# EEpromConfig.net
KiCad netlist of a schematic drawn in Altium Designer
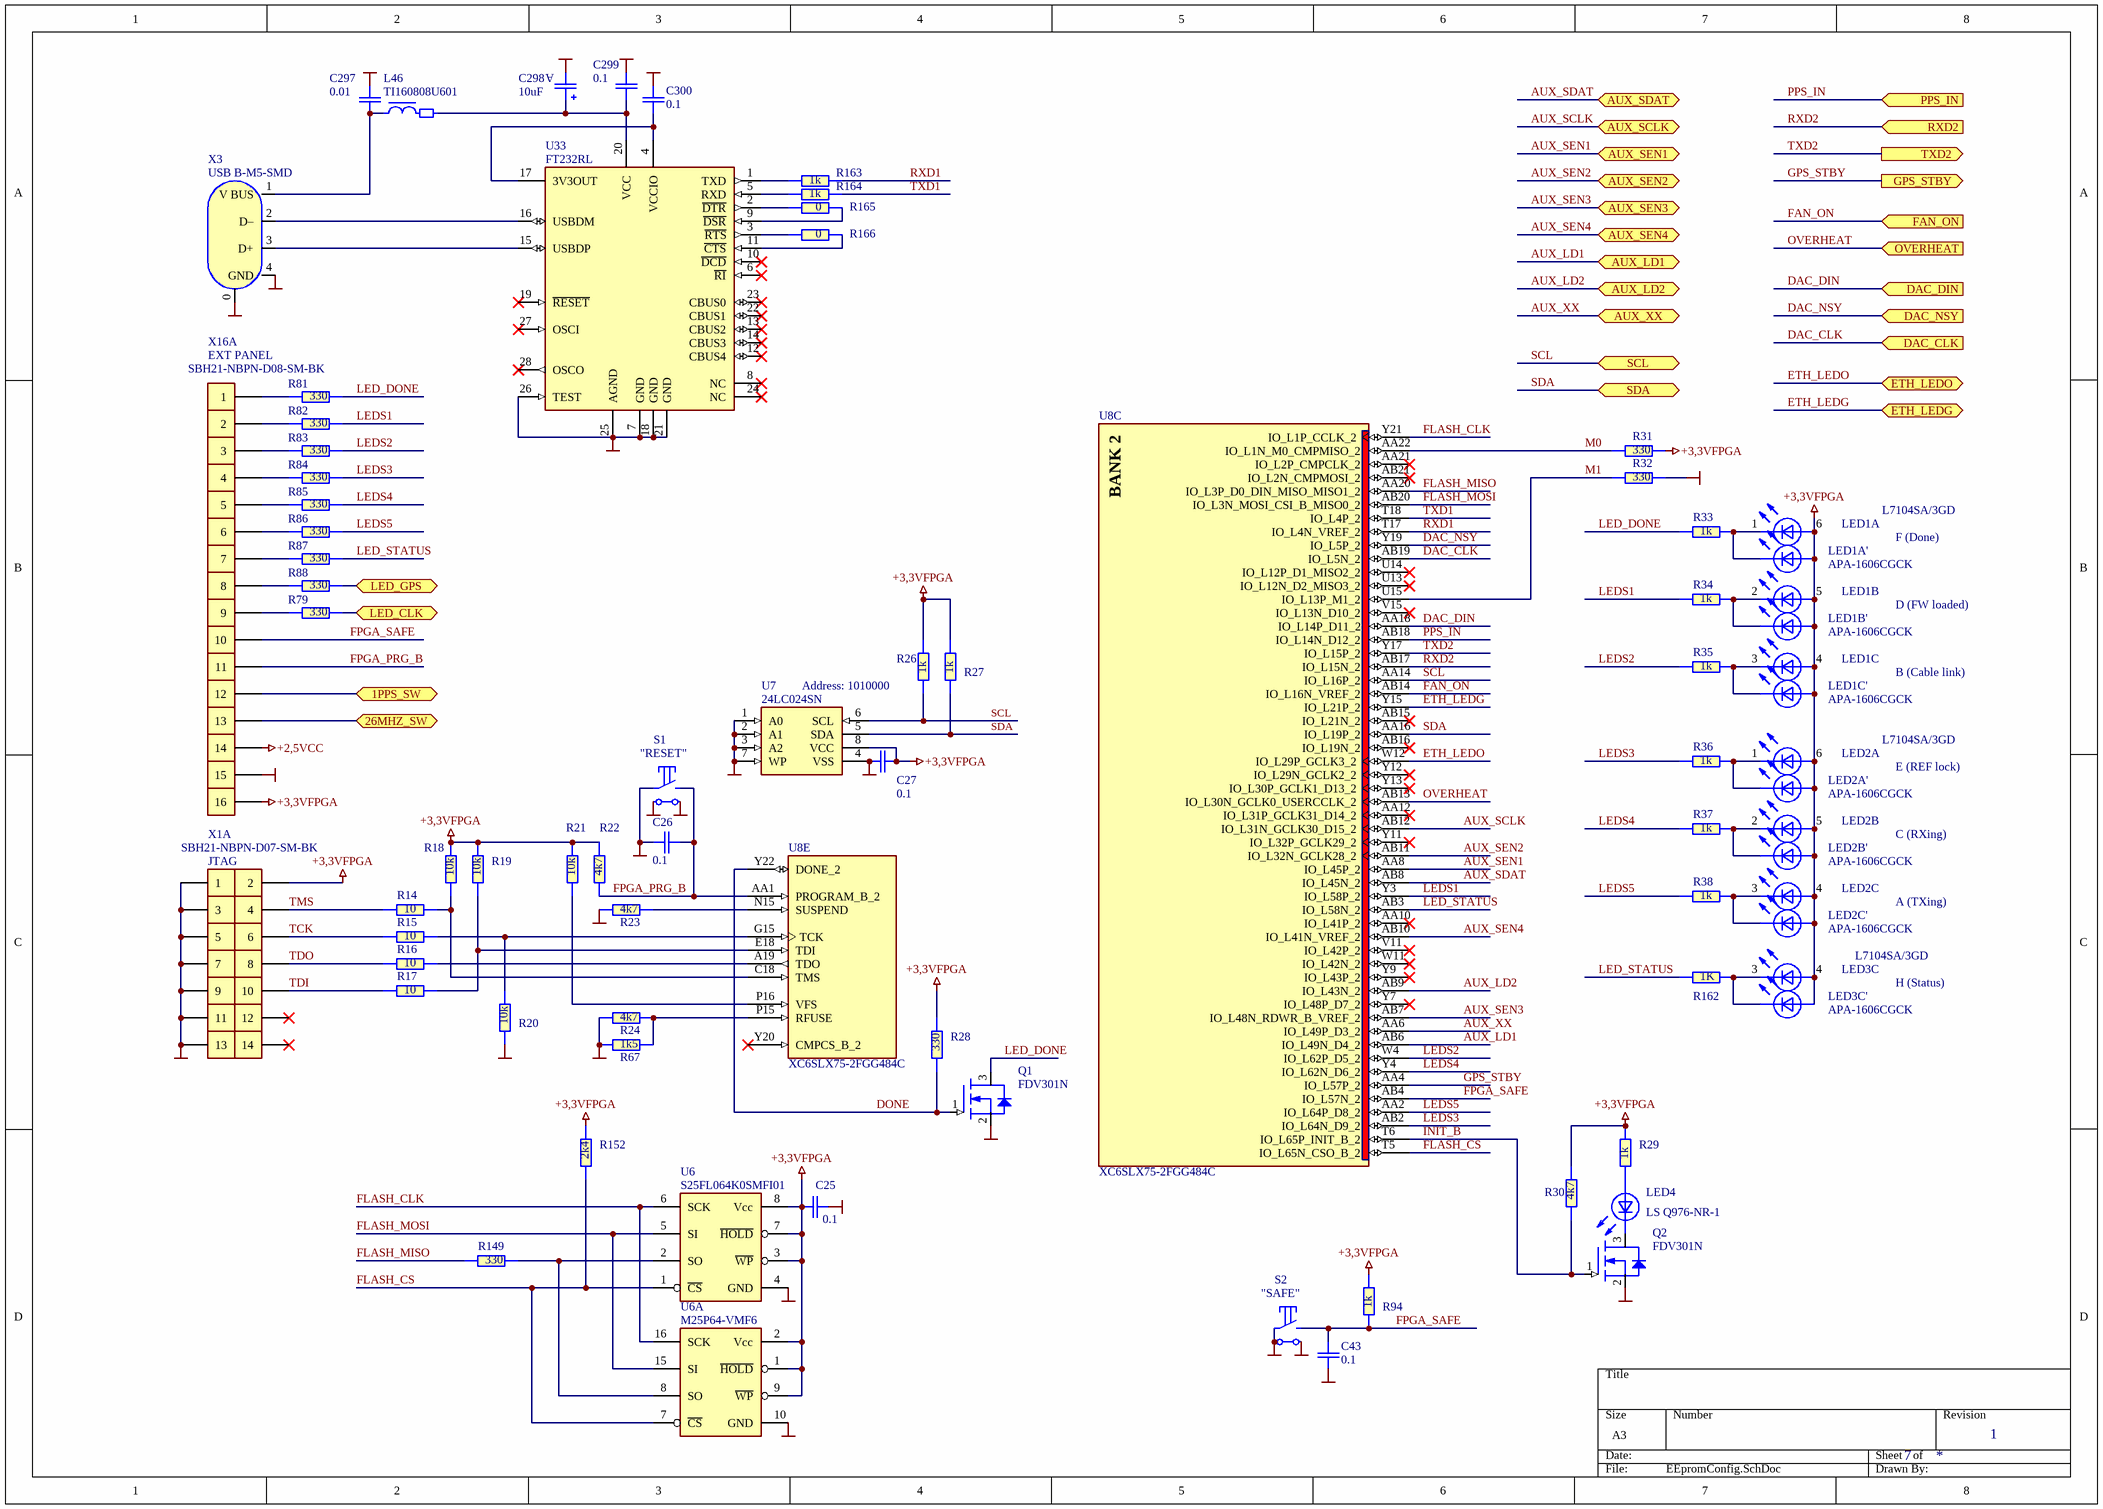
[diagram p0: EEpromConfig.SchDoc]

(export (version "E")
  (design (tool "Eeschema 10.0.6"))
  (components
    (comp (ref "C25")
      (value "0.1")
      (footprint "C0402-Phillips")
      (description "Конденсатор")
      (fields (field (name "MANUFACTURER") "MURATA") (field (name "TOLERANCE") "20%"))
      (libsource (lib "Capacitors") (part "C0402"))
    )
    (comp (ref "C26")
      (value "0.1")
      (footprint "C0402-Phillips")
      (description "Конденсатор")
      (fields (field (name "MANUFACTURER") "MURATA") (field (name "TOLERANCE") "20%"))
      (libsource (lib "Capacitors") (part "C0402"))
    )
    (comp (ref "C27")
      (value "0.1")
      (footprint "C0402-Phillips")
      (description "Конденсатор")
      (fields (field (name "MANUFACTURER") "MURATA") (field (name "TOLERANCE") "20%"))
      (libsource (lib "Capacitors") (part "C0402"))
    )
    (comp (ref "C43")
      (value "0.1")
      (footprint "C0402-Phillips")
      (description "Конденсатор")
      (fields (field (name "MANUFACTURER") "MURATA") (field (name "TOLERANCE") "20%"))
      (libsource (lib "Capacitors") (part "C0402"))
    )
    (comp (ref "C297")
      (value "0.01")
      (footprint "C0402-Phillips")
      (description "Конденсатор")
      (fields (field (name "MANUFACTURER") "MURATA") (field (name "TOLERANCE") "20%"))
      (libsource (lib "Capacitors") (part "C0402"))
    )
    (comp (ref "C298")
      (value "10uF")
      (footprint "CA3216")
      (description "Конденсатор")
      (fields (field (name "MANUFACTURER") "SPRAGUE"))
      (libsource (lib "Capacitors") (part "CA3216"))
    )
    (comp (ref "C299")
      (value "0.1")
      (footprint "C0402-Phillips")
      (description "Конденсатор")
      (fields (field (name "MANUFACTURER") "MURATA") (field (name "TOLERANCE") "20%"))
      (libsource (lib "Capacitors") (part "C0402"))
    )
    (comp (ref "C300")
      (value "0.1")
      (footprint "C0402-Phillips")
      (description "Конденсатор")
      (fields (field (name "MANUFACTURER") "MURATA") (field (name "TOLERANCE") "20%"))
      (libsource (lib "Capacitors") (part "C0402"))
    )
    (comp (ref "L46")
      (value "TI160808U601")
      (footprint "Ti160808-Phillips")
      (description "Дроссель ЭМС")
      (fields (field (name "MANUFACTURER") "MURATA"))
      (libsource (lib "altium-import") (part "root_0_TI160808_"))
    )
    (comp (ref "LED1")
      (value "L7104SA/3GD")
      (footprint "L-7104SA/3")
      (description "Светодиод")
      (fields (field (name "MANUFACTURER") "KINGBRIGTH"))
      (libsource (lib "Diods") (part "L7104SA/3"))
    )
    (comp (ref "LED1A'")
      (value "APA-1606CGCK")
      (footprint "KPA-1606g")
      (description "Светодиод")
      (fields (field (name "MANUFACTURER") "Kingbright"))
      (libsource (lib "Diods") (part "KPA-1606"))
    )
    (comp (ref "LED1B'")
      (value "APA-1606CGCK")
      (footprint "KPA-1606g")
      (description "Светодиод")
      (fields (field (name "MANUFACTURER") "Kingbright"))
      (libsource (lib "Diods") (part "KPA-1606"))
    )
    (comp (ref "LED1C'")
      (value "APA-1606CGCK")
      (footprint "KPA-1606g")
      (description "Светодиод")
      (fields (field (name "MANUFACTURER") "Kingbright"))
      (libsource (lib "Diods") (part "KPA-1606"))
    )
    (comp (ref "LED2")
      (value "L7104SA/3GD")
      (footprint "L-7104SA/3")
      (description "Светодиод")
      (fields (field (name "MANUFACTURER") "KINGBRIGTH"))
      (libsource (lib "Diods") (part "L7104SA/3"))
    )
    (comp (ref "LED2A'")
      (value "APA-1606CGCK")
      (footprint "KPA-1606g")
      (description "Светодиод")
      (fields (field (name "MANUFACTURER") "Kingbright"))
      (libsource (lib "Diods") (part "KPA-1606"))
    )
    (comp (ref "LED2B'")
      (value "APA-1606CGCK")
      (footprint "KPA-1606g")
      (description "Светодиод")
      (fields (field (name "MANUFACTURER") "Kingbright"))
      (libsource (lib "Diods") (part "KPA-1606"))
    )
    (comp (ref "LED2C'")
      (value "APA-1606CGCK")
      (footprint "KPA-1606g")
      (description "Светодиод")
      (fields (field (name "MANUFACTURER") "Kingbright"))
      (libsource (lib "Diods") (part "KPA-1606"))
    )
    (comp (ref "LED3")
      (value "L7104SA/3GD")
      (footprint "L-7104SA/3")
      (description "Светодиод")
      (fields (field (name "MANUFACTURER") "KINGBRIGTH"))
      (libsource (lib "Diods") (part "L7104SA/3"))
    )
    (comp (ref "LED3C'")
      (value "APA-1606CGCK")
      (footprint "KPA-1606g")
      (description "Светодиод")
      (fields (field (name "MANUFACTURER") "Kingbright"))
      (libsource (lib "Diods") (part "KPA-1606"))
    )
    (comp (ref "LED4")
      (value "LS Q976-NR-1")
      (footprint "LED-0603y")
      (description "LED SMD")
      (fields (field (name "MANUFACTURER") "OSRAM Opto Semiconductors Inc"))
      (libsource (lib "altium-import") (part "root_2_LED0603_"))
    )
    (comp (ref "Q1")
      (value "FDV301N")
      (footprint "SOT23-Philips")
      (description "Транзистор")
      (fields (field (name "MANUFACTURER") "Fairchild"))
      (libsource (lib "Transistors") (part "FDV301N"))
    )
    (comp (ref "Q2")
      (value "FDV301N")
      (footprint "SOT23-Philips")
      (description "Транзистор")
      (fields (field (name "MANUFACTURER") "Fairchild"))
      (libsource (lib "Transistors") (part "FDV301N"))
    )
    (comp (ref "R14")
      (value "10")
      (footprint "R0603-PHILLIPS")
      (description "Резистор")
      (fields (field (name "MANUFACTURER") "YAGEO") (field (name "TOLERANCE") "5%"))
      (libsource (lib "altium-import") (part "root_1_R0603_"))
    )
    (comp (ref "R15")
      (value "10")
      (footprint "R0603-PHILLIPS")
      (description "Резистор")
      (fields (field (name "MANUFACTURER") "YAGEO") (field (name "TOLERANCE") "5%"))
      (libsource (lib "altium-import") (part "root_1_R0603_"))
    )
    (comp (ref "R16")
      (value "10")
      (footprint "R0603-PHILLIPS")
      (description "Резистор")
      (fields (field (name "MANUFACTURER") "YAGEO") (field (name "TOLERANCE") "5%"))
      (libsource (lib "altium-import") (part "root_1_R0603_"))
    )
    (comp (ref "R17")
      (value "10")
      (footprint "R0603-PHILLIPS")
      (description "Резистор")
      (fields (field (name "MANUFACTURER") "YAGEO") (field (name "TOLERANCE") "5%"))
      (libsource (lib "altium-import") (part "root_1_R0603_"))
    )
    (comp (ref "R18")
      (value "10k")
      (footprint "R0603-PHILLIPS")
      (description "Резистор")
      (fields (field (name "MANUFACTURER") "YAGEO") (field (name "TOLERANCE") "5%"))
      (libsource (lib "altium-import") (part "root_0_R0603_"))
    )
    (comp (ref "R19")
      (value "10k")
      (footprint "R0603-PHILLIPS")
      (description "Резистор")
      (fields (field (name "MANUFACTURER") "YAGEO") (field (name "TOLERANCE") "5%"))
      (libsource (lib "altium-import") (part "root_0_R0603_"))
    )
    (comp (ref "R20")
      (value "10k")
      (footprint "R0603-PHILLIPS")
      (description "Резистор")
      (fields (field (name "MANUFACTURER") "YAGEO") (field (name "TOLERANCE") "5%"))
      (libsource (lib "altium-import") (part "root_0_R0603_"))
    )
    (comp (ref "R21")
      (value "10k")
      (footprint "R0603-PHILLIPS")
      (description "Резистор")
      (fields (field (name "MANUFACTURER") "YAGEO") (field (name "TOLERANCE") "5%"))
      (libsource (lib "altium-import") (part "root_0_R0603_"))
    )
    (comp (ref "R22")
      (value "4k7")
      (footprint "R0603-PHILLIPS")
      (description "Резистор")
      (fields (field (name "MANUFACTURER") "YAGEO") (field (name "TOLERANCE") "5%"))
      (libsource (lib "altium-import") (part "root_0_R0603_"))
    )
    (comp (ref "R23")
      (value "4k7")
      (footprint "R0603-PHILLIPS")
      (description "Резистор")
      (fields (field (name "MANUFACTURER") "YAGEO") (field (name "TOLERANCE") "5%"))
      (libsource (lib "altium-import") (part "root_1_R0603_"))
    )
    (comp (ref "R24")
      (value "4k7")
      (footprint "R0603-PHILLIPS")
      (description "Резистор")
      (fields (field (name "MANUFACTURER") "YAGEO") (field (name "TOLERANCE") "5%"))
      (libsource (lib "altium-import") (part "root_1_R0603_"))
    )
    (comp (ref "R26")
      (value "1k")
      (footprint "R0603-PHILLIPS")
      (description "Резистор")
      (fields (field (name "MANUFACTURER") "YAGEO") (field (name "TOLERANCE") "5%"))
      (libsource (lib "altium-import") (part "root_0_R0603_"))
    )
    (comp (ref "R27")
      (value "1k")
      (footprint "R0603-PHILLIPS")
      (description "Резистор")
      (fields (field (name "MANUFACTURER") "YAGEO") (field (name "TOLERANCE") "5%"))
      (libsource (lib "altium-import") (part "root_0_R0603_"))
    )
    (comp (ref "R28")
      (value "330")
      (footprint "R0603-PHILLIPS")
      (description "Резистор")
      (fields (field (name "MANUFACTURER") "YAGEO") (field (name "TOLERANCE") "5%"))
      (libsource (lib "altium-import") (part "root_0_R0603_"))
    )
    (comp (ref "R29")
      (value "1k")
      (footprint "R0603-PHILLIPS")
      (description "Резистор")
      (fields (field (name "MANUFACTURER") "YAGEO") (field (name "TOLERANCE") "5%"))
      (libsource (lib "altium-import") (part "root_0_R0603_"))
    )
    (comp (ref "R30")
      (value "4k7")
      (footprint "R0603-PHILLIPS")
      (description "Резистор")
      (fields (field (name "MANUFACTURER") "YAGEO") (field (name "TOLERANCE") "5%"))
      (libsource (lib "altium-import") (part "root_0_R0603_"))
    )
    (comp (ref "R31")
      (value "330")
      (footprint "R0603-PHILLIPS")
      (description "Резистор")
      (fields (field (name "MANUFACTURER") "YAGEO") (field (name "TOLERANCE") "5%"))
      (libsource (lib "altium-import") (part "root_1_R0603_"))
    )
    (comp (ref "R32")
      (value "330")
      (footprint "R0603-PHILLIPS")
      (description "Резистор")
      (fields (field (name "MANUFACTURER") "YAGEO") (field (name "TOLERANCE") "5%"))
      (libsource (lib "altium-import") (part "root_1_R0603_"))
    )
    (comp (ref "R33")
      (value "1k")
      (footprint "R0603-PHILLIPS")
      (description "Резистор")
      (fields (field (name "MANUFACTURER") "YAGEO") (field (name "TOLERANCE") "5%"))
      (libsource (lib "altium-import") (part "root_3_R0603_"))
    )
    (comp (ref "R34")
      (value "1k")
      (footprint "R0603-PHILLIPS")
      (description "Резистор")
      (fields (field (name "MANUFACTURER") "YAGEO") (field (name "TOLERANCE") "5%"))
      (libsource (lib "altium-import") (part "root_3_R0603_"))
    )
    (comp (ref "R35")
      (value "1k")
      (footprint "R0603-PHILLIPS")
      (description "Резистор")
      (fields (field (name "MANUFACTURER") "YAGEO") (field (name "TOLERANCE") "5%"))
      (libsource (lib "altium-import") (part "root_3_R0603_"))
    )
    (comp (ref "R36")
      (value "1k")
      (footprint "R0603-PHILLIPS")
      (description "Резистор")
      (fields (field (name "MANUFACTURER") "YAGEO") (field (name "TOLERANCE") "5%"))
      (libsource (lib "altium-import") (part "root_3_R0603_"))
    )
    (comp (ref "R37")
      (value "1k")
      (footprint "R0603-PHILLIPS")
      (description "Резистор")
      (fields (field (name "MANUFACTURER") "YAGEO") (field (name "TOLERANCE") "5%"))
      (libsource (lib "altium-import") (part "root_3_R0603_"))
    )
    (comp (ref "R38")
      (value "1k")
      (footprint "R0603-PHILLIPS")
      (description "Резистор")
      (fields (field (name "MANUFACTURER") "YAGEO") (field (name "TOLERANCE") "5%"))
      (libsource (lib "altium-import") (part "root_3_R0603_"))
    )
    (comp (ref "R67")
      (value "1k5")
      (footprint "R0603-PHILLIPS")
      (description "Резистор")
      (fields (field (name "MANUFACTURER") "YAGEO") (field (name "TOLERANCE") "5%"))
      (libsource (lib "altium-import") (part "root_1_R0603_"))
    )
    (comp (ref "R79")
      (value "330")
      (footprint "R0603-PHILLIPS")
      (description "Резистор")
      (fields (field (name "MANUFACTURER") "YAGEO") (field (name "TOLERANCE") "5%"))
      (libsource (lib "altium-import") (part "root_3_mirrored_R0603_"))
    )
    (comp (ref "R81")
      (value "330")
      (footprint "R0603-PHILLIPS")
      (description "Резистор")
      (fields (field (name "MANUFACTURER") "YAGEO") (field (name "TOLERANCE") "5%"))
      (libsource (lib "altium-import") (part "root_3_mirrored_R0603_"))
    )
    (comp (ref "R82")
      (value "330")
      (footprint "R0603-PHILLIPS")
      (description "Резистор")
      (fields (field (name "MANUFACTURER") "YAGEO") (field (name "TOLERANCE") "5%"))
      (libsource (lib "altium-import") (part "root_3_mirrored_R0603_"))
    )
    (comp (ref "R83")
      (value "330")
      (footprint "R0603-PHILLIPS")
      (description "Резистор")
      (fields (field (name "MANUFACTURER") "YAGEO") (field (name "TOLERANCE") "5%"))
      (libsource (lib "altium-import") (part "root_3_mirrored_R0603_"))
    )
    (comp (ref "R84")
      (value "330")
      (footprint "R0603-PHILLIPS")
      (description "Резистор")
      (fields (field (name "MANUFACTURER") "YAGEO") (field (name "TOLERANCE") "5%"))
      (libsource (lib "altium-import") (part "root_3_mirrored_R0603_"))
    )
    (comp (ref "R85")
      (value "330")
      (footprint "R0603-PHILLIPS")
      (description "Резистор")
      (fields (field (name "MANUFACTURER") "YAGEO") (field (name "TOLERANCE") "5%"))
      (libsource (lib "altium-import") (part "root_3_mirrored_R0603_"))
    )
    (comp (ref "R86")
      (value "330")
      (footprint "R0603-PHILLIPS")
      (description "Резистор")
      (fields (field (name "MANUFACTURER") "YAGEO") (field (name "TOLERANCE") "5%"))
      (libsource (lib "altium-import") (part "root_3_mirrored_R0603_"))
    )
    (comp (ref "R87")
      (value "330")
      (footprint "R0603-PHILLIPS")
      (description "Резистор")
      (fields (field (name "MANUFACTURER") "YAGEO") (field (name "TOLERANCE") "5%"))
      (libsource (lib "altium-import") (part "root_3_mirrored_R0603_"))
    )
    (comp (ref "R88")
      (value "330")
      (footprint "R0603-PHILLIPS")
      (description "Резистор")
      (fields (field (name "MANUFACTURER") "YAGEO") (field (name "TOLERANCE") "5%"))
      (libsource (lib "altium-import") (part "root_3_mirrored_R0603_"))
    )
    (comp (ref "R94")
      (value "1k")
      (footprint "R0603-PHILLIPS")
      (description "Резистор")
      (fields (field (name "MANUFACTURER") "YAGEO") (field (name "TOLERANCE") "5%"))
      (libsource (lib "altium-import") (part "root_0_R0603_"))
    )
    (comp (ref "R149")
      (value "330")
      (footprint "R0603-PHILLIPS")
      (description "Резистор")
      (fields (field (name "MANUFACTURER") "YAGEO") (field (name "TOLERANCE") "5%"))
      (libsource (lib "altium-import") (part "root_1_R0603_"))
    )
    (comp (ref "R152")
      (value "2k4")
      (footprint "R0603-PHILLIPS")
      (description "Резистор")
      (fields (field (name "MANUFACTURER") "YAGEO") (field (name "TOLERANCE") "5%"))
      (libsource (lib "altium-import") (part "root_0_R0603_"))
    )
    (comp (ref "R162")
      (value "1K")
      (footprint "R0603-PHILLIPS")
      (description "Резистор")
      (fields (field (name "MANUFACTURER") "YAGEO") (field (name "TOLERANCE") "5%"))
      (libsource (lib "altium-import") (part "root_1_R0603_"))
    )
    (comp (ref "R163")
      (value "1k")
      (footprint "R0603-PHILLIPS")
      (description "Резистор")
      (fields (field (name "MANUFACTURER") "YAGEO") (field (name "TOLERANCE") "5%"))
      (libsource (lib "altium-import") (part "root_3_R0603_"))
    )
    (comp (ref "R164")
      (value "1k")
      (footprint "R0603-PHILLIPS")
      (description "Резистор")
      (fields (field (name "MANUFACTURER") "YAGEO") (field (name "TOLERANCE") "5%"))
      (libsource (lib "altium-import") (part "root_3_R0603_"))
    )
    (comp (ref "R165")
      (value "0")
      (footprint "R0603-PHILLIPS")
      (description "Резистор")
      (fields (field (name "MANUFACTURER") "YAGEO") (field (name "TOLERANCE") "5%"))
      (libsource (lib "Resistors") (part "R0603"))
    )
    (comp (ref "R166")
      (value "0")
      (footprint "R0603-PHILLIPS")
      (description "Резистор")
      (fields (field (name "MANUFACTURER") "YAGEO") (field (name "TOLERANCE") "5%"))
      (libsource (lib "Resistors") (part "R0603"))
    )
    (comp (ref "S1")
      (value "TL3340AF160QG")
      (footprint "TL3340")
      (description "Switch Tactile SMD right angle")
      (fields (field (name "MANUFACTURER") "E-Switch") (field (name "MISC") "\"RESET\""))
      (libsource (lib "Andy") (part "TL3340AF160QG"))
    )
    (comp (ref "S2")
      (value "TL3340AF160QG")
      (footprint "TL3340")
      (description "Switch Tactile SMD right angle")
      (fields (field (name "MANUFACTURER") "E-Switch") (field (name "MISC") "\"SAFE\""))
      (libsource (lib "Andy") (part "TL3340AF160QG"))
    )
    (comp (ref "U6")
      (value "S25FL064K0SMFI01")
      (footprint "SO-8[wide200]")
      (description "Микросхема")
      (fields (field (name "MANUFACTURER") "SPANSION"))
      (libsource (lib "Andy") (part "S25FL064K"))
    )
    (comp (ref "U6A")
      (value "M25P64-VMF6")
      (footprint "so-16W")
      (description "Микросхема")
      (fields (field (name "MANUFACTURER") "ST"))
      (libsource (lib "Andy") (part "M25P64-VMF6"))
    )
    (comp (ref "U7")
      (value "24LC024SN")
      (footprint "SOIC8")
      (description "Микросхема")
      (fields (field (name "MANUFACTURER") "Microchip") (field (name "ADDRESS") "1010000"))
      (libsource (lib "altium-import") (part "root_0_AT24CXX_"))
    )
    (comp (ref "U8")
      (value "XC6SLX75-2FGG484C")
      (footprint "FBGA484")
      (fields (field (name "MANUFACTURER") "Xilinx"))
      (libsource (lib "MicroCircuitsM-Z") (part "XC6SLX75-2FGG484C"))
    )
    (comp (ref "U33")
      (value "FT232RL")
      (footprint "SSOP-28(5.3X10/0.65)")
      (description "Микросхема")
      (fields (field (name "MANUFACTURER") "FTDI"))
      (libsource (lib "Andy") (part "FT232RL"))
    )
    (comp (ref "X1")
      (value "SBH21-NBPN-D07-SM-BK")
      (footprint "SBH-14")
      (description "Разъем")
      (fields (field (name "MANUFACTURER") "Sullins") (field (name "OTHER") "JTAG"))
      (libsource (lib "Andy") (part "SBH21-7x2_SMD"))
    )
    (comp (ref "X3")
      (value "USB B-M5-SMD")
      (footprint "USB/SM0.8-6H5")
      (description "Разъём")
      (libsource (lib "Connectors") (part "USB M-1J"))
    )
    (comp (ref "X16")
      (value "SBH21-NBPN-D08-SM-BK")
      (footprint "SBH-16")
      (description "Connector 2mm SMD")
      (fields (field (name "MANUFACTURER") "Sullins") (field (name "MISC") "EXT PANEL"))
      (libsource (lib "Andy") (part "SBH21-8x2_SMD"))
    )
  )
  (nets
    (net (code "1") (name "+2,5VCC") (class "Default")
      (node (ref "X16") (pin "14") (pinfunction "14_14") (pintype "passive"))
    )
    (net (code "2") (name "+3,3VFPGA") (class "Default")
      (node (ref "C25") (pin "1") (pinfunction "1_1") (pintype "passive"))
      (node (ref "C27") (pin "2") (pinfunction "2_2") (pintype "passive"))
      (node (ref "LED1") (pin "4") (pinfunction "A3_4") (pintype "passive"))
      (node (ref "LED1") (pin "5") (pinfunction "A2_5") (pintype "passive"))
      (node (ref "LED1") (pin "6") (pinfunction "A1_6") (pintype "passive"))
      (node (ref "LED1A'") (pin "2") (pinfunction "A_2") (pintype "passive"))
      (node (ref "LED1B'") (pin "2") (pinfunction "A_2") (pintype "passive"))
      (node (ref "LED1C'") (pin "2") (pinfunction "A_2") (pintype "passive"))
      (node (ref "LED2") (pin "4") (pinfunction "A3_4") (pintype "passive"))
      (node (ref "LED2") (pin "5") (pinfunction "A2_5") (pintype "passive"))
      (node (ref "LED2") (pin "6") (pinfunction "A1_6") (pintype "passive"))
      (node (ref "LED2A'") (pin "2") (pinfunction "A_2") (pintype "passive"))
      (node (ref "LED2B'") (pin "2") (pinfunction "A_2") (pintype "passive"))
      (node (ref "LED2C'") (pin "2") (pinfunction "A_2") (pintype "passive"))
      (node (ref "LED3") (pin "4") (pinfunction "A3_4") (pintype "passive"))
      (node (ref "LED3C'") (pin "2") (pinfunction "A_2") (pintype "passive"))
      (node (ref "R152") (pin "1") (pinfunction "1_1") (pintype "passive"))
      (node (ref "R18") (pin "1") (pinfunction "1_1") (pintype "passive"))
      (node (ref "R19") (pin "1") (pinfunction "1_1") (pintype "passive"))
      (node (ref "R21") (pin "1") (pinfunction "1_1") (pintype "passive"))
      (node (ref "R22") (pin "1") (pinfunction "1_1") (pintype "passive"))
      (node (ref "R26") (pin "1") (pinfunction "1_1") (pintype "passive"))
      (node (ref "R27") (pin "1") (pinfunction "1_1") (pintype "passive"))
      (node (ref "R28") (pin "1") (pinfunction "1_1") (pintype "passive"))
      (node (ref "R29") (pin "1") (pinfunction "1_1") (pintype "passive"))
      (node (ref "R30") (pin "1") (pinfunction "1_1") (pintype "passive"))
      (node (ref "R31") (pin "2") (pinfunction "2_2") (pintype "passive"))
      (node (ref "R94") (pin "1") (pinfunction "1_1") (pintype "passive"))
      (node (ref "U6") (pin "3") (pinfunction "~{WP}_3") (pintype "passive"))
      (node (ref "U6") (pin "7") (pinfunction "~{HOLD}_7") (pintype "passive"))
      (node (ref "U6") (pin "8") (pinfunction "Vcc_8") (pintype "passive"))
      (node (ref "U6A") (pin "1") (pinfunction "~{HOLD}_1") (pintype "passive"))
      (node (ref "U6A") (pin "2") (pinfunction "Vcc_2") (pintype "passive"))
      (node (ref "U6A") (pin "9") (pinfunction "~{WP}_9") (pintype "passive"))
      (node (ref "U7") (pin "8") (pinfunction "VCC_8") (pintype "power_in"))
      (node (ref "X1") (pin "2") (pinfunction "2_2") (pintype "passive"))
      (node (ref "X16") (pin "16") (pinfunction "16_16") (pintype "passive"))
    )
    (net (code "3") (name "/1PPS_SW") (class "Default")
      (node (ref "X16") (pin "12") (pinfunction "12_12") (pintype "passive"))
    )
    (net (code "4") (name "/26MHZ_SW") (class "Default")
      (node (ref "X16") (pin "13") (pinfunction "13_13") (pintype "passive"))
    )
    (net (code "5") (name "/AUX_LD1") (class "Default")
      (node (ref "U8") (pin "AB6") (pinfunction "IO_L49N_D4_2_AB6") (pintype "bidirectional"))
    )
    (net (code "6") (name "/AUX_LD2") (class "Default")
      (node (ref "U8") (pin "AB9") (pinfunction "IO_L43N_2_AB9") (pintype "bidirectional"))
    )
    (net (code "7") (name "/AUX_SCLK") (class "Default")
      (node (ref "U8") (pin "AB12") (pinfunction "IO_L31N_GCLK30_D15_2_AB12") (pintype "bidirectional"))
    )
    (net (code "8") (name "/AUX_SDAT") (class "Default")
      (node (ref "U8") (pin "AB8") (pinfunction "IO_L45N_2_AB8") (pintype "bidirectional"))
    )
    (net (code "9") (name "/AUX_SEN1") (class "Default")
      (node (ref "U8") (pin "AA8") (pinfunction "IO_L45P_2_AA8") (pintype "bidirectional"))
    )
    (net (code "10") (name "/AUX_SEN2") (class "Default")
      (node (ref "U8") (pin "AB11") (pinfunction "IO_L32N_GCLK28_2_AB11") (pintype "bidirectional"))
    )
    (net (code "11") (name "/AUX_SEN3") (class "Default")
      (node (ref "U8") (pin "AB7") (pinfunction "IO_L48N_RDWR_B_VREF_2_AB7") (pintype "bidirectional"))
    )
    (net (code "12") (name "/AUX_SEN4") (class "Default")
      (node (ref "U8") (pin "AB10") (pinfunction "IO_L41N_VREF_2_AB10") (pintype "bidirectional"))
    )
    (net (code "13") (name "/AUX_XX") (class "Default")
      (node (ref "U8") (pin "AA6") (pinfunction "IO_L49P_D3_2_AA6") (pintype "bidirectional"))
    )
    (net (code "14") (name "/DAC_CLK") (class "Default")
      (node (ref "U8") (pin "AB19") (pinfunction "IO_L5N_2_AB19") (pintype "bidirectional"))
    )
    (net (code "15") (name "/DAC_DIN") (class "Default")
      (node (ref "U8") (pin "AA18") (pinfunction "IO_L14P_D11_2_AA18") (pintype "bidirectional"))
    )
    (net (code "16") (name "/DAC_NSY") (class "Default")
      (node (ref "U8") (pin "Y19") (pinfunction "IO_L5P_2_Y19") (pintype "bidirectional"))
    )
    (net (code "17") (name "/DONE") (class "Default")
      (node (ref "Q1") (pin "1") (pinfunction "G_1") (pintype "input"))
      (node (ref "R28") (pin "2") (pinfunction "2_2") (pintype "passive"))
      (node (ref "U8") (pin "Y22") (pinfunction "DONE_2_Y22") (pintype "bidirectional"))
    )
    (net (code "18") (name "/ETH_LEDG") (class "Default")
      (node (ref "U8") (pin "Y15") (pinfunction "IO_L21P_2_Y15") (pintype "bidirectional"))
    )
    (net (code "19") (name "/ETH_LEDO") (class "Default")
      (node (ref "U8") (pin "W12") (pinfunction "IO_L29P_GCLK3_2_W12") (pintype "bidirectional"))
    )
    (net (code "20") (name "/FAN_ON") (class "Default")
      (node (ref "U8") (pin "AB14") (pinfunction "IO_L16N_VREF_2_AB14") (pintype "bidirectional"))
    )
    (net (code "21") (name "/FLASH_CLK") (class "Default")
      (node (ref "U6") (pin "6") (pinfunction "SCK_6") (pintype "passive"))
      (node (ref "U6A") (pin "16") (pinfunction "SCK_16") (pintype "passive"))
      (node (ref "U8") (pin "Y21") (pinfunction "IO_L1P_CCLK_2_Y21") (pintype "bidirectional"))
    )
    (net (code "22") (name "/FLASH_CS") (class "Default")
      (node (ref "R152") (pin "2") (pinfunction "2_2") (pintype "passive"))
      (node (ref "U6") (pin "1") (pinfunction "~{CS}_1") (pintype "passive"))
      (node (ref "U6A") (pin "7") (pinfunction "~{CS}_7") (pintype "passive"))
      (node (ref "U8") (pin "T5") (pinfunction "IO_L65N_CSO_B_2_T5") (pintype "bidirectional"))
    )
    (net (code "23") (name "/FLASH_MISO") (class "Default")
      (node (ref "R149") (pin "1") (pinfunction "1_1") (pintype "passive"))
      (node (ref "U8") (pin "AA20") (pinfunction "IO_L3P_D0_DIN_MISO_MISO1_2_AA20") (pintype "bidirectional"))
    )
    (net (code "24") (name "/FLASH_MOSI") (class "Default")
      (node (ref "U6") (pin "5") (pinfunction "SI_5") (pintype "passive"))
      (node (ref "U6A") (pin "15") (pinfunction "SI_15") (pintype "passive"))
      (node (ref "U8") (pin "AB20") (pinfunction "IO_L3N_MOSI_CSI_B_MISO0_2_AB20") (pintype "bidirectional"))
    )
    (net (code "25") (name "/FPGA_PRG_B") (class "Default")
      (node (ref "C26") (pin "1") (pinfunction "1_1") (pintype "passive"))
      (node (ref "R22") (pin "2") (pinfunction "2_2") (pintype "passive"))
      (node (ref "S1") (pin "1") (pinfunction "1_1") (pintype "passive"))
      (node (ref "U8") (pin "AA1") (pinfunction "PROGRAM_B_2_AA1") (pintype "input"))
      (node (ref "X16") (pin "11") (pinfunction "11_11") (pintype "passive"))
    )
    (net (code "26") (name "/FPGA_SAFE") (class "Default")
      (node (ref "C43") (pin "2") (pinfunction "2_2") (pintype "passive"))
      (node (ref "R94") (pin "2") (pinfunction "2_2") (pintype "passive"))
      (node (ref "S2") (pin "1") (pinfunction "1_1") (pintype "passive"))
      (node (ref "U8") (pin "AB4") (pinfunction "IO_L57N_2_AB4") (pintype "bidirectional"))
      (node (ref "X16") (pin "10") (pinfunction "10_10") (pintype "passive"))
    )
    (net (code "27") (name "/GPS_STBY") (class "Default")
      (node (ref "U8") (pin "AA4") (pinfunction "IO_L57P_2_AA4") (pintype "bidirectional"))
    )
    (net (code "28") (name "/INIT_B") (class "Default")
      (node (ref "Q2") (pin "1") (pinfunction "G_1") (pintype "input"))
      (node (ref "R30") (pin "2") (pinfunction "2_2") (pintype "passive"))
      (node (ref "U8") (pin "T6") (pinfunction "IO_L65P_INIT_B_2_T6") (pintype "bidirectional"))
    )
    (net (code "29") (name "/LEDS1") (class "Default")
      (node (ref "R34") (pin "2") (pinfunction "2_2") (pintype "passive"))
      (node (ref "R82") (pin "2") (pinfunction "2_2") (pintype "passive"))
      (node (ref "U8") (pin "Y3") (pinfunction "IO_L58P_2_Y3") (pintype "bidirectional"))
    )
    (net (code "30") (name "/LEDS2") (class "Default")
      (node (ref "R35") (pin "2") (pinfunction "2_2") (pintype "passive"))
      (node (ref "R83") (pin "2") (pinfunction "2_2") (pintype "passive"))
      (node (ref "U8") (pin "W4") (pinfunction "IO_L62P_D5_2_W4") (pintype "bidirectional"))
    )
    (net (code "31") (name "/LEDS3") (class "Default")
      (node (ref "R36") (pin "2") (pinfunction "2_2") (pintype "passive"))
      (node (ref "R84") (pin "2") (pinfunction "2_2") (pintype "passive"))
      (node (ref "U8") (pin "AB2") (pinfunction "IO_L64N_D9_2_AB2") (pintype "bidirectional"))
    )
    (net (code "32") (name "/LEDS4") (class "Default")
      (node (ref "R37") (pin "2") (pinfunction "2_2") (pintype "passive"))
      (node (ref "R85") (pin "2") (pinfunction "2_2") (pintype "passive"))
      (node (ref "U8") (pin "Y4") (pinfunction "IO_L62N_D6_2_Y4") (pintype "bidirectional"))
    )
    (net (code "33") (name "/LEDS5") (class "Default")
      (node (ref "R38") (pin "2") (pinfunction "2_2") (pintype "passive"))
      (node (ref "R86") (pin "2") (pinfunction "2_2") (pintype "passive"))
      (node (ref "U8") (pin "AA2") (pinfunction "IO_L64P_D8_2_AA2") (pintype "bidirectional"))
    )
    (net (code "34") (name "/LED_CLK") (class "Default")
      (node (ref "R79") (pin "2") (pinfunction "2_2") (pintype "passive"))
    )
    (net (code "35") (name "/LED_DONE") (class "Default")
      (node (ref "Q1") (pin "3") (pinfunction "D_3") (pintype "passive"))
      (node (ref "R33") (pin "2") (pinfunction "2_2") (pintype "passive"))
      (node (ref "R81") (pin "2") (pinfunction "2_2") (pintype "passive"))
    )
    (net (code "36") (name "/LED_GPS") (class "Default")
      (node (ref "R88") (pin "2") (pinfunction "2_2") (pintype "passive"))
    )
    (net (code "37") (name "/LED_STATUS") (class "Default")
      (node (ref "R162") (pin "1") (pinfunction "1_1") (pintype "passive"))
      (node (ref "R87") (pin "2") (pinfunction "2_2") (pintype "passive"))
      (node (ref "U8") (pin "AB3") (pinfunction "IO_L58N_2_AB3") (pintype "bidirectional"))
    )
    (net (code "38") (name "/M0") (class "Default")
      (node (ref "R31") (pin "1") (pinfunction "1_1") (pintype "passive"))
      (node (ref "U8") (pin "AA22") (pinfunction "IO_L1N_M0_CMPMISO_2_AA22") (pintype "bidirectional"))
    )
    (net (code "39") (name "/M1") (class "Default")
      (node (ref "R32") (pin "1") (pinfunction "1_1") (pintype "passive"))
      (node (ref "U8") (pin "U15") (pinfunction "IO_L13P_M1_2_U15") (pintype "bidirectional"))
    )
    (net (code "40") (name "/OVERHEAT") (class "Default")
      (node (ref "U8") (pin "AB13") (pinfunction "IO_L30N_GCLK0_USERCCLK_2_AB13") (pintype "bidirectional"))
    )
    (net (code "41") (name "/PPS_IN") (class "Default")
      (node (ref "U8") (pin "AB18") (pinfunction "IO_L14N_D12_2_AB18") (pintype "bidirectional"))
    )
    (net (code "42") (name "/RXD1") (class "Default")
      (node (ref "R163") (pin "1") (pinfunction "1_1") (pintype "passive"))
      (node (ref "U8") (pin "T17") (pinfunction "IO_L4N_VREF_2_T17") (pintype "bidirectional"))
    )
    (net (code "43") (name "/RXD2") (class "Default")
      (node (ref "U8") (pin "AB17") (pinfunction "IO_L15N_2_AB17") (pintype "bidirectional"))
    )
    (net (code "44") (name "/SCL") (class "Default")
      (node (ref "R26") (pin "2") (pinfunction "2_2") (pintype "passive"))
      (node (ref "U7") (pin "6") (pinfunction "SCL_6") (pintype "input"))
      (node (ref "U8") (pin "AA14") (pinfunction "IO_L16P_2_AA14") (pintype "bidirectional"))
    )
    (net (code "45") (name "/SDA") (class "Default")
      (node (ref "R27") (pin "2") (pinfunction "2_2") (pintype "passive"))
      (node (ref "U7") (pin "5") (pinfunction "SDA_5") (pintype "passive"))
      (node (ref "U8") (pin "AA16") (pinfunction "IO_L19P_2_AA16") (pintype "bidirectional"))
    )
    (net (code "46") (name "/TCK") (class "Default")
      (node (ref "R15") (pin "1") (pinfunction "1_1") (pintype "passive"))
      (node (ref "X1") (pin "6") (pinfunction "6_6") (pintype "passive"))
    )
    (net (code "47") (name "/TDI") (class "Default")
      (node (ref "R17") (pin "1") (pinfunction "1_1") (pintype "passive"))
      (node (ref "X1") (pin "10") (pinfunction "10_10") (pintype "passive"))
    )
    (net (code "48") (name "/TDO") (class "Default")
      (node (ref "R16") (pin "1") (pinfunction "1_1") (pintype "passive"))
      (node (ref "X1") (pin "8") (pinfunction "8_8") (pintype "passive"))
    )
    (net (code "49") (name "/TMS") (class "Default")
      (node (ref "R14") (pin "1") (pinfunction "1_1") (pintype "passive"))
      (node (ref "X1") (pin "4") (pinfunction "4_4") (pintype "passive"))
    )
    (net (code "50") (name "/TXD1") (class "Default")
      (node (ref "R164") (pin "1") (pinfunction "1_1") (pintype "passive"))
      (node (ref "U8") (pin "T18") (pinfunction "IO_L4P_2_T18") (pintype "bidirectional"))
    )
    (net (code "51") (name "/TXD2") (class "Default")
      (node (ref "U8") (pin "Y17") (pinfunction "IO_L15P_2_Y17") (pintype "bidirectional"))
    )
    (net (code "52") (name "GND") (class "Default")
      (node (ref "C25") (pin "2") (pinfunction "2_2") (pintype "passive"))
      (node (ref "C26") (pin "2") (pinfunction "2_2") (pintype "passive"))
      (node (ref "C27") (pin "1") (pinfunction "1_1") (pintype "passive"))
      (node (ref "C297") (pin "1") (pinfunction "1_1") (pintype "passive"))
      (node (ref "C298") (pin "2") (pinfunction "-_2") (pintype "passive"))
      (node (ref "C299") (pin "2") (pinfunction "2_2") (pintype "passive"))
      (node (ref "C300") (pin "2") (pinfunction "2_2") (pintype "passive"))
      (node (ref "C43") (pin "1") (pinfunction "1_1") (pintype "passive"))
      (node (ref "Q1") (pin "2") (pinfunction "S_2") (pintype "passive"))
      (node (ref "Q2") (pin "2") (pinfunction "S_2") (pintype "passive"))
      (node (ref "R20") (pin "2") (pinfunction "2_2") (pintype "passive"))
      (node (ref "R23") (pin "1") (pinfunction "1_1") (pintype "passive"))
      (node (ref "R24") (pin "1") (pinfunction "1_1") (pintype "passive"))
      (node (ref "R32") (pin "2") (pinfunction "2_2") (pintype "passive"))
      (node (ref "R67") (pin "1") (pinfunction "1_1") (pintype "passive"))
      (node (ref "S1") (pin "2") (pinfunction "2_2") (pintype "passive"))
      (node (ref "S1") (pin "3") (pinfunction "3_3") (pintype "passive"))
      (node (ref "S1") (pin "4") (pinfunction "4_4") (pintype "passive"))
      (node (ref "S2") (pin "2") (pinfunction "2_2") (pintype "passive"))
      (node (ref "S2") (pin "3") (pinfunction "3_3") (pintype "passive"))
      (node (ref "S2") (pin "4") (pinfunction "4_4") (pintype "passive"))
      (node (ref "U33") (pin "18") (pinfunction "GND_18") (pintype "power_in"))
      (node (ref "U33") (pin "21") (pinfunction "GND_21") (pintype "power_in"))
      (node (ref "U33") (pin "25") (pinfunction "AGND_25") (pintype "power_in"))
      (node (ref "U33") (pin "26") (pinfunction "TEST_26") (pintype "input"))
      (node (ref "U33") (pin "7") (pinfunction "GND_7") (pintype "power_in"))
      (node (ref "U6") (pin "4") (pinfunction "GND_4") (pintype "passive"))
      (node (ref "U6A") (pin "10") (pinfunction "GND_10") (pintype "passive"))
      (node (ref "U7") (pin "1") (pinfunction "A0_1") (pintype "input"))
      (node (ref "U7") (pin "2") (pinfunction "A1_2") (pintype "input"))
      (node (ref "U7") (pin "3") (pinfunction "A2_3") (pintype "input"))
      (node (ref "U7") (pin "4") (pinfunction "VSS_4") (pintype "power_in"))
      (node (ref "U7") (pin "7") (pinfunction "WP_7") (pintype "input"))
      (node (ref "X1") (pin "1") (pinfunction "1_1") (pintype "passive"))
      (node (ref "X1") (pin "11") (pinfunction "11_11") (pintype "passive"))
      (node (ref "X1") (pin "13") (pinfunction "13_13") (pintype "passive"))
      (node (ref "X1") (pin "3") (pinfunction "3_3") (pintype "passive"))
      (node (ref "X1") (pin "5") (pinfunction "5_5") (pintype "passive"))
      (node (ref "X1") (pin "7") (pinfunction "7_7") (pintype "passive"))
      (node (ref "X1") (pin "9") (pinfunction "9_9") (pintype "passive"))
      (node (ref "X16") (pin "15") (pinfunction "15_15") (pintype "passive"))
      (node (ref "X3") (pin "0") (pinfunction "GND_0") (pintype "power_in"))
      (node (ref "X3") (pin "4") (pinfunction "GND_4") (pintype "power_in"))
    )
    (net (code "53") (name "Net-(C298-+)") (class "Default")
      (node (ref "C298") (pin "1") (pinfunction "+_1") (pintype "passive"))
      (node (ref "C299") (pin "1") (pinfunction "1_1") (pintype "passive"))
      (node (ref "L46") (pin "2") (pinfunction "2_2") (pintype "passive"))
      (node (ref "U33") (pin "20") (pinfunction "VCC_20") (pintype "power_in"))
    )
    (net (code "54") (name "Net-(LED1A'-K)") (class "Default")
      (node (ref "LED1") (pin "1") (pinfunction "K1_1") (pintype "passive"))
      (node (ref "LED1A'") (pin "1") (pinfunction "K_1") (pintype "passive"))
      (node (ref "R33") (pin "1") (pinfunction "1_1") (pintype "passive"))
    )
    (net (code "55") (name "Net-(LED1B'-K)") (class "Default")
      (node (ref "LED1") (pin "2") (pinfunction "K2_2") (pintype "passive"))
      (node (ref "LED1B'") (pin "1") (pinfunction "K_1") (pintype "passive"))
      (node (ref "R34") (pin "1") (pinfunction "1_1") (pintype "passive"))
    )
    (net (code "56") (name "Net-(LED1C'-K)") (class "Default")
      (node (ref "LED1") (pin "3") (pinfunction "K3_3") (pintype "passive"))
      (node (ref "LED1C'") (pin "1") (pinfunction "K_1") (pintype "passive"))
      (node (ref "R35") (pin "1") (pinfunction "1_1") (pintype "passive"))
    )
    (net (code "57") (name "Net-(LED2A'-K)") (class "Default")
      (node (ref "LED2") (pin "1") (pinfunction "K1_1") (pintype "passive"))
      (node (ref "LED2A'") (pin "1") (pinfunction "K_1") (pintype "passive"))
      (node (ref "R36") (pin "1") (pinfunction "1_1") (pintype "passive"))
    )
    (net (code "58") (name "Net-(LED2B'-K)") (class "Default")
      (node (ref "LED2") (pin "2") (pinfunction "K2_2") (pintype "passive"))
      (node (ref "LED2B'") (pin "1") (pinfunction "K_1") (pintype "passive"))
      (node (ref "R37") (pin "1") (pinfunction "1_1") (pintype "passive"))
    )
    (net (code "59") (name "Net-(LED2C'-K)") (class "Default")
      (node (ref "LED2") (pin "3") (pinfunction "K3_3") (pintype "passive"))
      (node (ref "LED2C'") (pin "1") (pinfunction "K_1") (pintype "passive"))
      (node (ref "R38") (pin "1") (pinfunction "1_1") (pintype "passive"))
    )
    (net (code "60") (name "Net-(LED3C'-K)") (class "Default")
      (node (ref "LED3") (pin "3") (pinfunction "K3_3") (pintype "passive"))
      (node (ref "LED3C'") (pin "1") (pinfunction "K_1") (pintype "passive"))
      (node (ref "R162") (pin "2") (pinfunction "2_2") (pintype "passive"))
    )
    (net (code "61") (name "Net-(LED4-A)") (class "Default")
      (node (ref "LED4") (pin "2") (pinfunction "A_2") (pintype "passive"))
      (node (ref "R29") (pin "2") (pinfunction "2_2") (pintype "passive"))
    )
    (net (code "62") (name "Net-(LED4-K)") (class "Default")
      (node (ref "LED4") (pin "1") (pinfunction "K_1") (pintype "passive"))
      (node (ref "Q2") (pin "3") (pinfunction "D_3") (pintype "passive"))
    )
    (net (code "63") (name "Net-(R79-Pad1)") (class "Default")
      (node (ref "R79") (pin "1") (pinfunction "1_1") (pintype "passive"))
      (node (ref "X16") (pin "9") (pinfunction "9_9") (pintype "passive"))
    )
    (net (code "64") (name "Net-(R81-Pad1)") (class "Default")
      (node (ref "R81") (pin "1") (pinfunction "1_1") (pintype "passive"))
      (node (ref "X16") (pin "1") (pinfunction "1_1") (pintype "passive"))
    )
    (net (code "65") (name "Net-(R82-Pad1)") (class "Default")
      (node (ref "R82") (pin "1") (pinfunction "1_1") (pintype "passive"))
      (node (ref "X16") (pin "2") (pinfunction "2_2") (pintype "passive"))
    )
    (net (code "66") (name "Net-(R83-Pad1)") (class "Default")
      (node (ref "R83") (pin "1") (pinfunction "1_1") (pintype "passive"))
      (node (ref "X16") (pin "3") (pinfunction "3_3") (pintype "passive"))
    )
    (net (code "67") (name "Net-(R84-Pad1)") (class "Default")
      (node (ref "R84") (pin "1") (pinfunction "1_1") (pintype "passive"))
      (node (ref "X16") (pin "4") (pinfunction "4_4") (pintype "passive"))
    )
    (net (code "68") (name "Net-(R85-Pad1)") (class "Default")
      (node (ref "R85") (pin "1") (pinfunction "1_1") (pintype "passive"))
      (node (ref "X16") (pin "5") (pinfunction "5_5") (pintype "passive"))
    )
    (net (code "69") (name "Net-(R86-Pad1)") (class "Default")
      (node (ref "R86") (pin "1") (pinfunction "1_1") (pintype "passive"))
      (node (ref "X16") (pin "6") (pinfunction "6_6") (pintype "passive"))
    )
    (net (code "70") (name "Net-(R87-Pad1)") (class "Default")
      (node (ref "R87") (pin "1") (pinfunction "1_1") (pintype "passive"))
      (node (ref "X16") (pin "7") (pinfunction "7_7") (pintype "passive"))
    )
    (net (code "71") (name "Net-(R88-Pad1)") (class "Default")
      (node (ref "R88") (pin "1") (pinfunction "1_1") (pintype "passive"))
      (node (ref "X16") (pin "8") (pinfunction "8_8") (pintype "passive"))
    )
    (net (code "72") (name "Net-(U6-SO)") (class "Default")
      (node (ref "R149") (pin "2") (pinfunction "2_2") (pintype "passive"))
      (node (ref "U6") (pin "2") (pinfunction "SO_2") (pintype "passive"))
      (node (ref "U6A") (pin "8") (pinfunction "SO_8") (pintype "passive"))
    )
    (net (code "73") (name "Net-(U8E-RFUSE)") (class "Default")
      (node (ref "R24") (pin "2") (pinfunction "2_2") (pintype "passive"))
      (node (ref "R67") (pin "2") (pinfunction "2_2") (pintype "passive"))
      (node (ref "U8") (pin "P15") (pinfunction "RFUSE_P15") (pintype "input"))
    )
    (net (code "74") (name "Net-(U8E-SUSPEND)") (class "Default")
      (node (ref "R23") (pin "2") (pinfunction "2_2") (pintype "passive"))
      (node (ref "U8") (pin "N15") (pinfunction "SUSPEND_N15") (pintype "input"))
    )
    (net (code "75") (name "Net-(U8E-TCK)") (class "Default")
      (node (ref "R15") (pin "2") (pinfunction "2_2") (pintype "passive"))
      (node (ref "R20") (pin "1") (pinfunction "1_1") (pintype "passive"))
      (node (ref "U8") (pin "G15") (pinfunction "TCK_G15") (pintype "input"))
    )
    (net (code "76") (name "Net-(U8E-TDI)") (class "Default")
      (node (ref "R17") (pin "2") (pinfunction "2_2") (pintype "passive"))
      (node (ref "R19") (pin "2") (pinfunction "2_2") (pintype "passive"))
      (node (ref "U8") (pin "E18") (pinfunction "TDI_E18") (pintype "input"))
    )
    (net (code "77") (name "Net-(U8E-TDO)") (class "Default")
      (node (ref "R16") (pin "2") (pinfunction "2_2") (pintype "passive"))
      (node (ref "U8") (pin "A19") (pinfunction "TDO_A19") (pintype "output"))
    )
    (net (code "78") (name "Net-(U8E-TMS)") (class "Default")
      (node (ref "R14") (pin "2") (pinfunction "2_2") (pintype "passive"))
      (node (ref "R18") (pin "2") (pinfunction "2_2") (pintype "passive"))
      (node (ref "U8") (pin "C18") (pinfunction "TMS_C18") (pintype "input"))
    )
    (net (code "79") (name "Net-(U8E-VFS)") (class "Default")
      (node (ref "R21") (pin "2") (pinfunction "2_2") (pintype "passive"))
      (node (ref "U8") (pin "P16") (pinfunction "VFS_P16") (pintype "input"))
    )
    (net (code "80") (name "Net-(U33-3V3OUT)") (class "Default")
      (node (ref "C300") (pin "1") (pinfunction "1_1") (pintype "passive"))
      (node (ref "U33") (pin "17") (pinfunction "3V3OUT_17") (pintype "power_in"))
      (node (ref "U33") (pin "4") (pinfunction "VCCIO_4") (pintype "power_in"))
    )
    (net (code "81") (name "Net-(U33-RXD)") (class "Default")
      (node (ref "R164") (pin "2") (pinfunction "2_2") (pintype "passive"))
      (node (ref "U33") (pin "5") (pinfunction "RXD_5") (pintype "input"))
    )
    (net (code "82") (name "Net-(U33-TXD)") (class "Default")
      (node (ref "R163") (pin "2") (pinfunction "2_2") (pintype "passive"))
      (node (ref "U33") (pin "1") (pinfunction "TXD_1") (pintype "output"))
    )
    (net (code "83") (name "Net-(U33-USBDM)") (class "Default")
      (node (ref "U33") (pin "16") (pinfunction "USBDM_16") (pintype "bidirectional"))
      (node (ref "X3") (pin "2") (pinfunction "D_2") (pintype "bidirectional"))
    )
    (net (code "84") (name "Net-(U33-USBDP)") (class "Default")
      (node (ref "U33") (pin "15") (pinfunction "USBDP_15") (pintype "bidirectional"))
      (node (ref "X3") (pin "3") (pinfunction "D+_3") (pintype "bidirectional"))
    )
    (net (code "85") (name "Net-(U33-~{CTS})") (class "Default")
      (node (ref "R166") (pin "2") (pinfunction "2_2") (pintype "passive"))
      (node (ref "U33") (pin "11") (pinfunction "~{CTS}_11") (pintype "input"))
    )
    (net (code "86") (name "Net-(U33-~{DSR})") (class "Default")
      (node (ref "R165") (pin "2") (pinfunction "2_2") (pintype "passive"))
      (node (ref "U33") (pin "9") (pinfunction "~{DSR}_9") (pintype "input"))
    )
    (net (code "87") (name "Net-(U33-~{DTR})") (class "Default")
      (node (ref "R165") (pin "1") (pinfunction "1_1") (pintype "passive"))
      (node (ref "U33") (pin "2") (pinfunction "~{DTR}_2") (pintype "output"))
    )
    (net (code "88") (name "Net-(U33-~{RTS})") (class "Default")
      (node (ref "R166") (pin "1") (pinfunction "1_1") (pintype "passive"))
      (node (ref "U33") (pin "3") (pinfunction "~{RTS}_3") (pintype "output"))
    )
    (net (code "89") (name "Net-(X3-V_BUS)") (class "Default")
      (node (ref "C297") (pin "2") (pinfunction "2_2") (pintype "passive"))
      (node (ref "L46") (pin "1") (pinfunction "1_1") (pintype "passive"))
      (node (ref "X3") (pin "1") (pinfunction "V_BUS_1") (pintype "power_in"))
    )
    (net (code "90") (name "unconnected-(U8C-IO_L2N_CMPMOSI_2-PadAB21)") (class "Default")
      (node (ref "U8") (pin "AB21") (pinfunction "IO_L2N_CMPMOSI_2_AB21") (pintype "bidirectional+no_connect"))
    )
    (net (code "91") (name "unconnected-(U8C-IO_L2P_CMPCLK_2-PadAA21)") (class "Default")
      (node (ref "U8") (pin "AA21") (pinfunction "IO_L2P_CMPCLK_2_AA21") (pintype "bidirectional+no_connect"))
    )
    (net (code "92") (name "unconnected-(U8C-IO_L12N_D2_MISO3_2-PadU13)") (class "Default")
      (node (ref "U8") (pin "U13") (pinfunction "IO_L12N_D2_MISO3_2_U13") (pintype "bidirectional+no_connect"))
    )
    (net (code "93") (name "unconnected-(U8C-IO_L12P_D1_MISO2_2-PadU14)") (class "Default")
      (node (ref "U8") (pin "U14") (pinfunction "IO_L12P_D1_MISO2_2_U14") (pintype "bidirectional+no_connect"))
    )
    (net (code "94") (name "unconnected-(U8C-IO_L13N_D10_2-PadV15)") (class "Default")
      (node (ref "U8") (pin "V15") (pinfunction "IO_L13N_D10_2_V15") (pintype "bidirectional+no_connect"))
    )
    (net (code "95") (name "unconnected-(U8C-IO_L19N_2-PadAB16)") (class "Default")
      (node (ref "U8") (pin "AB16") (pinfunction "IO_L19N_2_AB16") (pintype "bidirectional+no_connect"))
    )
    (net (code "96") (name "unconnected-(U8C-IO_L21N_2-PadAB15)") (class "Default")
      (node (ref "U8") (pin "AB15") (pinfunction "IO_L21N_2_AB15") (pintype "bidirectional+no_connect"))
    )
    (net (code "97") (name "unconnected-(U8C-IO_L29N_GCLK2_2-PadY12)") (class "Default")
      (node (ref "U8") (pin "Y12") (pinfunction "IO_L29N_GCLK2_2_Y12") (pintype "bidirectional+no_connect"))
    )
    (net (code "98") (name "unconnected-(U8C-IO_L30P_GCLK1_D13_2-PadY13)") (class "Default")
      (node (ref "U8") (pin "Y13") (pinfunction "IO_L30P_GCLK1_D13_2_Y13") (pintype "bidirectional+no_connect"))
    )
    (net (code "99") (name "unconnected-(U8C-IO_L31P_GCLK31_D14_2-PadAA12)") (class "Default")
      (node (ref "U8") (pin "AA12") (pinfunction "IO_L31P_GCLK31_D14_2_AA12") (pintype "bidirectional+no_connect"))
    )
    (net (code "100") (name "unconnected-(U8C-IO_L32P_GCLK29_2-PadY11)") (class "Default")
      (node (ref "U8") (pin "Y11") (pinfunction "IO_L32P_GCLK29_2_Y11") (pintype "bidirectional+no_connect"))
    )
    (net (code "101") (name "unconnected-(U8C-IO_L41P_2-PadAA10)") (class "Default")
      (node (ref "U8") (pin "AA10") (pinfunction "IO_L41P_2_AA10") (pintype "bidirectional+no_connect"))
    )
    (net (code "102") (name "unconnected-(U8C-IO_L42N_2-PadW11)") (class "Default")
      (node (ref "U8") (pin "W11") (pinfunction "IO_L42N_2_W11") (pintype "bidirectional+no_connect"))
    )
    (net (code "103") (name "unconnected-(U8C-IO_L42P_2-PadV11)") (class "Default")
      (node (ref "U8") (pin "V11") (pinfunction "IO_L42P_2_V11") (pintype "bidirectional+no_connect"))
    )
    (net (code "104") (name "unconnected-(U8C-IO_L43P_2-PadY9)") (class "Default")
      (node (ref "U8") (pin "Y9") (pinfunction "IO_L43P_2_Y9") (pintype "bidirectional+no_connect"))
    )
    (net (code "105") (name "unconnected-(U8C-IO_L48P_D7_2-PadY7)") (class "Default")
      (node (ref "U8") (pin "Y7") (pinfunction "IO_L48P_D7_2_Y7") (pintype "bidirectional+no_connect"))
    )
    (net (code "106") (name "unconnected-(U8E-CMPCS_B_2-PadY20)") (class "Default")
      (node (ref "U8") (pin "Y20") (pinfunction "CMPCS_B_2_Y20") (pintype "input+no_connect"))
    )
    (net (code "107") (name "unconnected-(U33-CBUS0-Pad23)") (class "Default")
      (node (ref "U33") (pin "23") (pinfunction "CBUS0_23") (pintype "bidirectional+no_connect"))
    )
    (net (code "108") (name "unconnected-(U33-CBUS1-Pad22)") (class "Default")
      (node (ref "U33") (pin "22") (pinfunction "CBUS1_22") (pintype "bidirectional+no_connect"))
    )
    (net (code "109") (name "unconnected-(U33-CBUS2-Pad13)") (class "Default")
      (node (ref "U33") (pin "13") (pinfunction "CBUS2_13") (pintype "bidirectional+no_connect"))
    )
    (net (code "110") (name "unconnected-(U33-CBUS3-Pad14)") (class "Default")
      (node (ref "U33") (pin "14") (pinfunction "CBUS3_14") (pintype "bidirectional+no_connect"))
    )
    (net (code "111") (name "unconnected-(U33-CBUS4-Pad12)") (class "Default")
      (node (ref "U33") (pin "12") (pinfunction "CBUS4_12") (pintype "bidirectional+no_connect"))
    )
    (net (code "112") (name "unconnected-(U33-NC-Pad8)") (class "Default")
      (node (ref "U33") (pin "8") (pinfunction "NC_8") (pintype "passive+no_connect"))
    )
    (net (code "113") (name "unconnected-(U33-NC-Pad24)") (class "Default")
      (node (ref "U33") (pin "24") (pinfunction "NC_24") (pintype "passive+no_connect"))
    )
    (net (code "114") (name "unconnected-(U33-OSCI-Pad27)") (class "Default")
      (node (ref "U33") (pin "27") (pinfunction "OSCI_27") (pintype "input+no_connect"))
    )
    (net (code "115") (name "unconnected-(U33-OSCO-Pad28)") (class "Default")
      (node (ref "U33") (pin "28") (pinfunction "OSCO_28") (pintype "output+no_connect"))
    )
    (net (code "116") (name "unconnected-(U33-~{DCD}-Pad10)") (class "Default")
      (node (ref "U33") (pin "10") (pinfunction "~{DCD}_10") (pintype "input+no_connect"))
    )
    (net (code "117") (name "unconnected-(U33-~{RESET}-Pad19)") (class "Default")
      (node (ref "U33") (pin "19") (pinfunction "~{RESET}_19") (pintype "input+no_connect"))
    )
    (net (code "118") (name "unconnected-(U33-~{RI}-Pad6)") (class "Default")
      (node (ref "U33") (pin "6") (pinfunction "~{RI}_6") (pintype "input+no_connect"))
    )
    (net (code "119") (name "unconnected-(X1-Pad12)") (class "Default")
      (node (ref "X1") (pin "12") (pinfunction "12_12") (pintype "passive+no_connect"))
    )
    (net (code "120") (name "unconnected-(X1-Pad14)") (class "Default")
      (node (ref "X1") (pin "14") (pinfunction "14_14") (pintype "passive+no_connect"))
    )
  )
)
